# Bandpass.net
KiCad netlist of a schematic drawn in Altium Designer
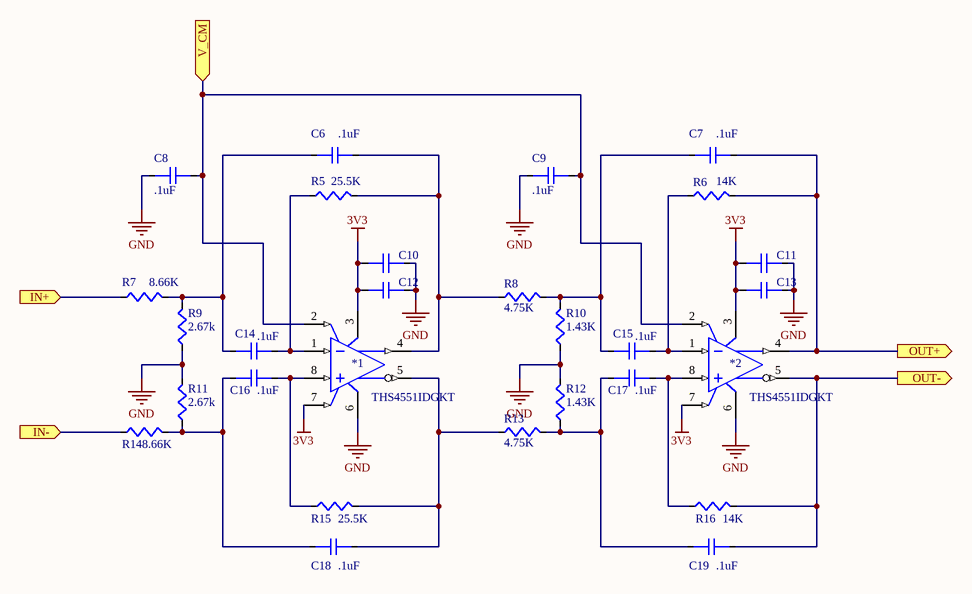
[diagram p0: Bandpass.SchDoc]

(export (version "E")
  (design (tool "Eeschema 10.0.6"))
  (components
    (comp (ref "*1")
      (value "THS4551IDGKT")
      (description "Low Noise, Precision, 150MHz, Fully Differential Amplifier 8-VSSOP -40 to 125")
      (libsource (lib "DAQ") (part "THS4551IDGKT"))
    )
    (comp (ref "*2")
      (value "THS4551IDGKT")
      (description "Low Noise, Precision, 150MHz, Fully Differential Amplifier 8-VSSOP -40 to 125")
      (libsource (lib "DAQ") (part "THS4551IDGKT"))
    )
    (comp (ref "C6")
      (value ".1uF")
      (description "0603 0.1 uF 16 V ±5 % Tolerance X7R SMT Multilayer Ceramic Chip Capacitor")
      (fields (field (name "TOLERANCE") "5%"))
      (libsource (lib "DAQ") (part "VJ0603Y104JXJCW1BC"))
    )
    (comp (ref "C7")
      (value ".1uF")
      (description "0603 0.1 uF 16 V ±5 % Tolerance X7R SMT Multilayer Ceramic Chip Capacitor")
      (fields (field (name "TOLERANCE") "5%"))
      (libsource (lib "DAQ") (part "VJ0603Y104JXJCW1BC"))
    )
    (comp (ref "C8")
      (value ".1uF")
      (description "0603 0.1 uF 16 V ±5 % Tolerance X7R SMT Multilayer Ceramic Chip Capacitor")
      (fields (field (name "TOLERANCE") "5%"))
      (libsource (lib "DAQ") (part "VJ0603Y104JXJCW1BC"))
    )
    (comp (ref "C9")
      (value ".1uF")
      (description "0603 0.1 uF 16 V ±5 % Tolerance X7R SMT Multilayer Ceramic Chip Capacitor")
      (fields (field (name "TOLERANCE") "5%"))
      (libsource (lib "DAQ") (part "VJ0603Y104JXJCW1BC"))
    )
    (comp (ref "C10")
      (value "2.2uF")
      (description "Cap Ceramic 0.22uF 16V X7R 10% SMD 0603 125C Paper T/R")
      (fields (field (name "TOLERANCE") "10%"))
      (libsource (lib "DAQ") (part "VJ0603Y224KXJCW1BC"))
    )
    (comp (ref "C11")
      (value "2.2uF")
      (description "Cap Ceramic 0.22uF 16V X7R 10% SMD 0603 125C Paper T/R")
      (fields (field (name "TOLERANCE") "10%"))
      (libsource (lib "DAQ") (part "VJ0603Y224KXJCW1BC"))
    )
    (comp (ref "C12")
      (value ".1uF")
      (description "0603 0.1 uF 16 V ±5 % Tolerance X7R SMT Multilayer Ceramic Chip Capacitor")
      (fields (field (name "TOLERANCE") "5%"))
      (libsource (lib "DAQ") (part "VJ0603Y104JXJCW1BC"))
    )
    (comp (ref "C13")
      (value ".1uF")
      (description "0603 0.1 uF 16 V ±5 % Tolerance X7R SMT Multilayer Ceramic Chip Capacitor")
      (fields (field (name "TOLERANCE") "5%"))
      (libsource (lib "DAQ") (part "VJ0603Y104JXJCW1BC"))
    )
    (comp (ref "C14")
      (value ".1uF")
      (description "0603 0.1 uF 16 V ±5 % Tolerance X7R SMT Multilayer Ceramic Chip Capacitor")
      (fields (field (name "TOLERANCE") "5%"))
      (libsource (lib "DAQ") (part "VJ0603Y104JXJCW1BC"))
    )
    (comp (ref "C15")
      (value ".1uF")
      (description "0603 0.1 uF 16 V ±5 % Tolerance X7R SMT Multilayer Ceramic Chip Capacitor")
      (fields (field (name "TOLERANCE") "5%"))
      (libsource (lib "DAQ") (part "VJ0603Y104JXJCW1BC"))
    )
    (comp (ref "C16")
      (value ".1uF")
      (description "0603 0.1 uF 16 V ±5 % Tolerance X7R SMT Multilayer Ceramic Chip Capacitor")
      (fields (field (name "TOLERANCE") "5%"))
      (libsource (lib "DAQ") (part "VJ0603Y104JXJCW1BC"))
    )
    (comp (ref "C17")
      (value ".1uF")
      (description "0603 0.1 uF 16 V ±5 % Tolerance X7R SMT Multilayer Ceramic Chip Capacitor")
      (fields (field (name "TOLERANCE") "5%"))
      (libsource (lib "DAQ") (part "VJ0603Y104JXJCW1BC"))
    )
    (comp (ref "C18")
      (value ".1uF")
      (description "0603 0.1 uF 16 V ±5 % Tolerance X7R SMT Multilayer Ceramic Chip Capacitor")
      (fields (field (name "TOLERANCE") "5%"))
      (libsource (lib "DAQ") (part "VJ0603Y104JXJCW1BC"))
    )
    (comp (ref "C19")
      (value ".1uF")
      (description "0603 0.1 uF 16 V ±5 % Tolerance X7R SMT Multilayer Ceramic Chip Capacitor")
      (fields (field (name "TOLERANCE") "5%"))
      (libsource (lib "DAQ") (part "VJ0603Y104JXJCW1BC"))
    )
    (comp (ref "R5")
      (value "25.5K")
      (description "RESISTOR, 25K5, 0603, 0.1%, 0.1W")
      (fields (field (name "TOLERANCE") "0.1%"))
      (libsource (lib "DAQ") (part "ERA-3AEB2552V"))
    )
    (comp (ref "R6")
      (value "14K")
      (description "Res Thin Film 0603 14K Ohm 0.1% 1/10W ±25ppm/°C Molded SMD SMD Paper T/R")
      (fields (field (name "TOLERANCE") "0.1%"))
      (libsource (lib "DAQ") (part "TNPW060314K0BEEA"))
    )
    (comp (ref "R7")
      (value "8.66K")
      (description "RES 8.66K OHM 1/10W 0.1% 0603")
      (fields (field (name "TOLERANCE") "0.1%"))
      (libsource (lib "DAQ") (part "TNPW06038K66BEEA"))
    )
    (comp (ref "R8")
      (value "4.75K")
      (description "Res Thin Film 0603 4.75K Ohm 0.1% 1/10W ±25ppm/°C Molded SMD SMD Paper T/R")
      (fields (field (name "TOLERANCE") "0.1%"))
      (libsource (lib "DAQ") (part "TNPW06034K75BEEA"))
    )
    (comp (ref "R9")
      (value "2.67k")
      (description "RES SMD 2.67KOHM 0.1% 1/10W 0603")
      (fields (field (name "TOLERANCE") "0.1%"))
      (libsource (lib "DAQ") (part "TNPW06032K67BEEA"))
    )
    (comp (ref "R10")
      (value "1.43K")
      (description "Res Thin Film 0603 1.43K Ohm 0.1% 1/10W ±25ppm/°C Molded SMD SMD Paper T/R")
      (fields (field (name "TOLERANCE") "0.1%"))
      (libsource (lib "DAQ") (part "TNPW06031K43BEEA"))
    )
    (comp (ref "R11")
      (value "2.67k")
      (description "RES SMD 2.67KOHM 0.1% 1/10W 0603")
      (fields (field (name "TOLERANCE") "0.1%"))
      (libsource (lib "DAQ") (part "TNPW06032K67BEEA"))
    )
    (comp (ref "R12")
      (value "1.43K")
      (description "Res Thin Film 0603 1.43K Ohm 0.1% 1/10W ±25ppm/°C Molded SMD SMD Paper T/R")
      (fields (field (name "TOLERANCE") "0.1%"))
      (libsource (lib "DAQ") (part "TNPW06031K43BEEA"))
    )
    (comp (ref "R13")
      (value "4.75K")
      (description "Res Thin Film 0603 4.75K Ohm 0.1% 1/10W ±25ppm/°C Molded SMD SMD Paper T/R")
      (fields (field (name "TOLERANCE") "0.1%"))
      (libsource (lib "DAQ") (part "TNPW06034K75BEEA"))
    )
    (comp (ref "R14")
      (value "8.66K")
      (description "RES 8.66K OHM 1/10W 0.1% 0603")
      (fields (field (name "TOLERANCE") "0.1%"))
      (libsource (lib "DAQ") (part "TNPW06038K66BEEA"))
    )
    (comp (ref "R15")
      (value "25.5K")
      (description "RESISTOR, 25K5, 0603, 0.1%, 0.1W")
      (fields (field (name "TOLERANCE") "0.1%"))
      (libsource (lib "DAQ") (part "ERA-3AEB2552V"))
    )
    (comp (ref "R16")
      (value "14K")
      (description "Res Thin Film 0603 14K Ohm 0.1% 1/10W ±25ppm/°C Molded SMD SMD Paper T/R")
      (fields (field (name "TOLERANCE") "0.1%"))
      (libsource (lib "DAQ") (part "TNPW060314K0BEEA"))
    )
  )
  (nets
    (net (code "1") (name "/IN+") (class "Default")
      (node (ref "R7") (pin "1") (pinfunction "1_1") (pintype "passive"))
    )
    (net (code "2") (name "/IN-") (class "Default")
      (node (ref "R14") (pin "1") (pinfunction "1_1") (pintype "passive"))
    )
    (net (code "3") (name "/OUT+") (class "Default")
      (node (ref "*2") (pin "4") (pinfunction "VOUT+_4") (pintype "output"))
      (node (ref "C7") (pin "2") (pinfunction "2_2") (pintype "passive"))
      (node (ref "R6") (pin "2") (pinfunction "2_2") (pintype "passive"))
    )
    (net (code "4") (name "/OUT-") (class "Default")
      (node (ref "*2") (pin "5") (pinfunction "VOUT-_5") (pintype "output"))
      (node (ref "C19") (pin "2") (pinfunction "2_2") (pintype "passive"))
      (node (ref "R16") (pin "2") (pinfunction "2_2") (pintype "passive"))
    )
    (net (code "5") (name "/V_CM") (class "Default")
      (node (ref "*1") (pin "2") (pinfunction "VOCM_2") (pintype "input"))
      (node (ref "*2") (pin "2") (pinfunction "VOCM_2") (pintype "input"))
      (node (ref "C8") (pin "2") (pinfunction "2_2") (pintype "passive"))
      (node (ref "C9") (pin "2") (pinfunction "2_2") (pintype "passive"))
    )
    (net (code "6") (name "3V3") (class "Default")
      (node (ref "*1") (pin "3") (pinfunction "VS+_3") (pintype "power_in"))
      (node (ref "*1") (pin "7") (pinfunction "~{PD}_7") (pintype "input"))
      (node (ref "*2") (pin "3") (pinfunction "VS+_3") (pintype "power_in"))
      (node (ref "*2") (pin "7") (pinfunction "~{PD}_7") (pintype "input"))
      (node (ref "C10") (pin "1") (pinfunction "1_1") (pintype "passive"))
      (node (ref "C11") (pin "1") (pinfunction "1_1") (pintype "passive"))
      (node (ref "C12") (pin "1") (pinfunction "1_1") (pintype "passive"))
      (node (ref "C13") (pin "1") (pinfunction "1_1") (pintype "passive"))
    )
    (net (code "7") (name "GND") (class "Default")
      (node (ref "*1") (pin "6") (pinfunction "VS-_6") (pintype "power_in"))
      (node (ref "*2") (pin "6") (pinfunction "VS-_6") (pintype "power_in"))
      (node (ref "C10") (pin "2") (pinfunction "2_2") (pintype "passive"))
      (node (ref "C11") (pin "2") (pinfunction "2_2") (pintype "passive"))
      (node (ref "C12") (pin "2") (pinfunction "2_2") (pintype "passive"))
      (node (ref "C13") (pin "2") (pinfunction "2_2") (pintype "passive"))
      (node (ref "C8") (pin "1") (pinfunction "1_1") (pintype "passive"))
      (node (ref "C9") (pin "1") (pinfunction "1_1") (pintype "passive"))
      (node (ref "R10") (pin "1") (pinfunction "1_1") (pintype "passive"))
      (node (ref "R11") (pin "2") (pinfunction "2_2") (pintype "passive"))
      (node (ref "R12") (pin "2") (pinfunction "2_2") (pintype "passive"))
      (node (ref "R9") (pin "1") (pinfunction "1_1") (pintype "passive"))
    )
    (net (code "8") (name "Net-(*1-VIN+)") (class "Default")
      (node (ref "*1") (pin "8") (pinfunction "VIN+_8") (pintype "input"))
      (node (ref "C16") (pin "2") (pinfunction "2_2") (pintype "passive"))
      (node (ref "R15") (pin "1") (pinfunction "1_1") (pintype "passive"))
    )
    (net (code "9") (name "Net-(*1-VIN-)") (class "Default")
      (node (ref "*1") (pin "1") (pinfunction "VIN-_1") (pintype "input"))
      (node (ref "C14") (pin "2") (pinfunction "2_2") (pintype "passive"))
      (node (ref "R5") (pin "1") (pinfunction "1_1") (pintype "passive"))
    )
    (net (code "10") (name "Net-(*1-VOUT+)") (class "Default")
      (node (ref "*1") (pin "4") (pinfunction "VOUT+_4") (pintype "output"))
      (node (ref "C6") (pin "2") (pinfunction "2_2") (pintype "passive"))
      (node (ref "R5") (pin "2") (pinfunction "2_2") (pintype "passive"))
      (node (ref "R8") (pin "1") (pinfunction "1_1") (pintype "passive"))
    )
    (net (code "11") (name "Net-(*1-VOUT-)") (class "Default")
      (node (ref "*1") (pin "5") (pinfunction "VOUT-_5") (pintype "output"))
      (node (ref "C18") (pin "2") (pinfunction "2_2") (pintype "passive"))
      (node (ref "R13") (pin "1") (pinfunction "1_1") (pintype "passive"))
      (node (ref "R15") (pin "2") (pinfunction "2_2") (pintype "passive"))
    )
    (net (code "12") (name "Net-(*2-VIN+)") (class "Default")
      (node (ref "*2") (pin "8") (pinfunction "VIN+_8") (pintype "input"))
      (node (ref "C17") (pin "2") (pinfunction "2_2") (pintype "passive"))
      (node (ref "R16") (pin "1") (pinfunction "1_1") (pintype "passive"))
    )
    (net (code "13") (name "Net-(*2-VIN-)") (class "Default")
      (node (ref "*2") (pin "1") (pinfunction "VIN-_1") (pintype "input"))
      (node (ref "C15") (pin "2") (pinfunction "2_2") (pintype "passive"))
      (node (ref "R6") (pin "1") (pinfunction "1_1") (pintype "passive"))
    )
    (net (code "14") (name "Net-(C14-Pad1)") (class "Default")
      (node (ref "C14") (pin "1") (pinfunction "1_1") (pintype "passive"))
      (node (ref "C6") (pin "1") (pinfunction "1_1") (pintype "passive"))
      (node (ref "R7") (pin "2") (pinfunction "2_2") (pintype "passive"))
      (node (ref "R9") (pin "2") (pinfunction "2_2") (pintype "passive"))
    )
    (net (code "15") (name "Net-(C15-Pad1)") (class "Default")
      (node (ref "C15") (pin "1") (pinfunction "1_1") (pintype "passive"))
      (node (ref "C7") (pin "1") (pinfunction "1_1") (pintype "passive"))
      (node (ref "R10") (pin "2") (pinfunction "2_2") (pintype "passive"))
      (node (ref "R8") (pin "2") (pinfunction "2_2") (pintype "passive"))
    )
    (net (code "16") (name "Net-(C16-Pad1)") (class "Default")
      (node (ref "C16") (pin "1") (pinfunction "1_1") (pintype "passive"))
      (node (ref "C18") (pin "1") (pinfunction "1_1") (pintype "passive"))
      (node (ref "R11") (pin "1") (pinfunction "1_1") (pintype "passive"))
      (node (ref "R14") (pin "2") (pinfunction "2_2") (pintype "passive"))
    )
    (net (code "17") (name "Net-(C17-Pad1)") (class "Default")
      (node (ref "C17") (pin "1") (pinfunction "1_1") (pintype "passive"))
      (node (ref "C19") (pin "1") (pinfunction "1_1") (pintype "passive"))
      (node (ref "R12") (pin "1") (pinfunction "1_1") (pintype "passive"))
      (node (ref "R13") (pin "2") (pinfunction "2_2") (pintype "passive"))
    )
  )
)
